# 4028_bcd.net
KiCad netlist of a schematic drawn in EAGLE
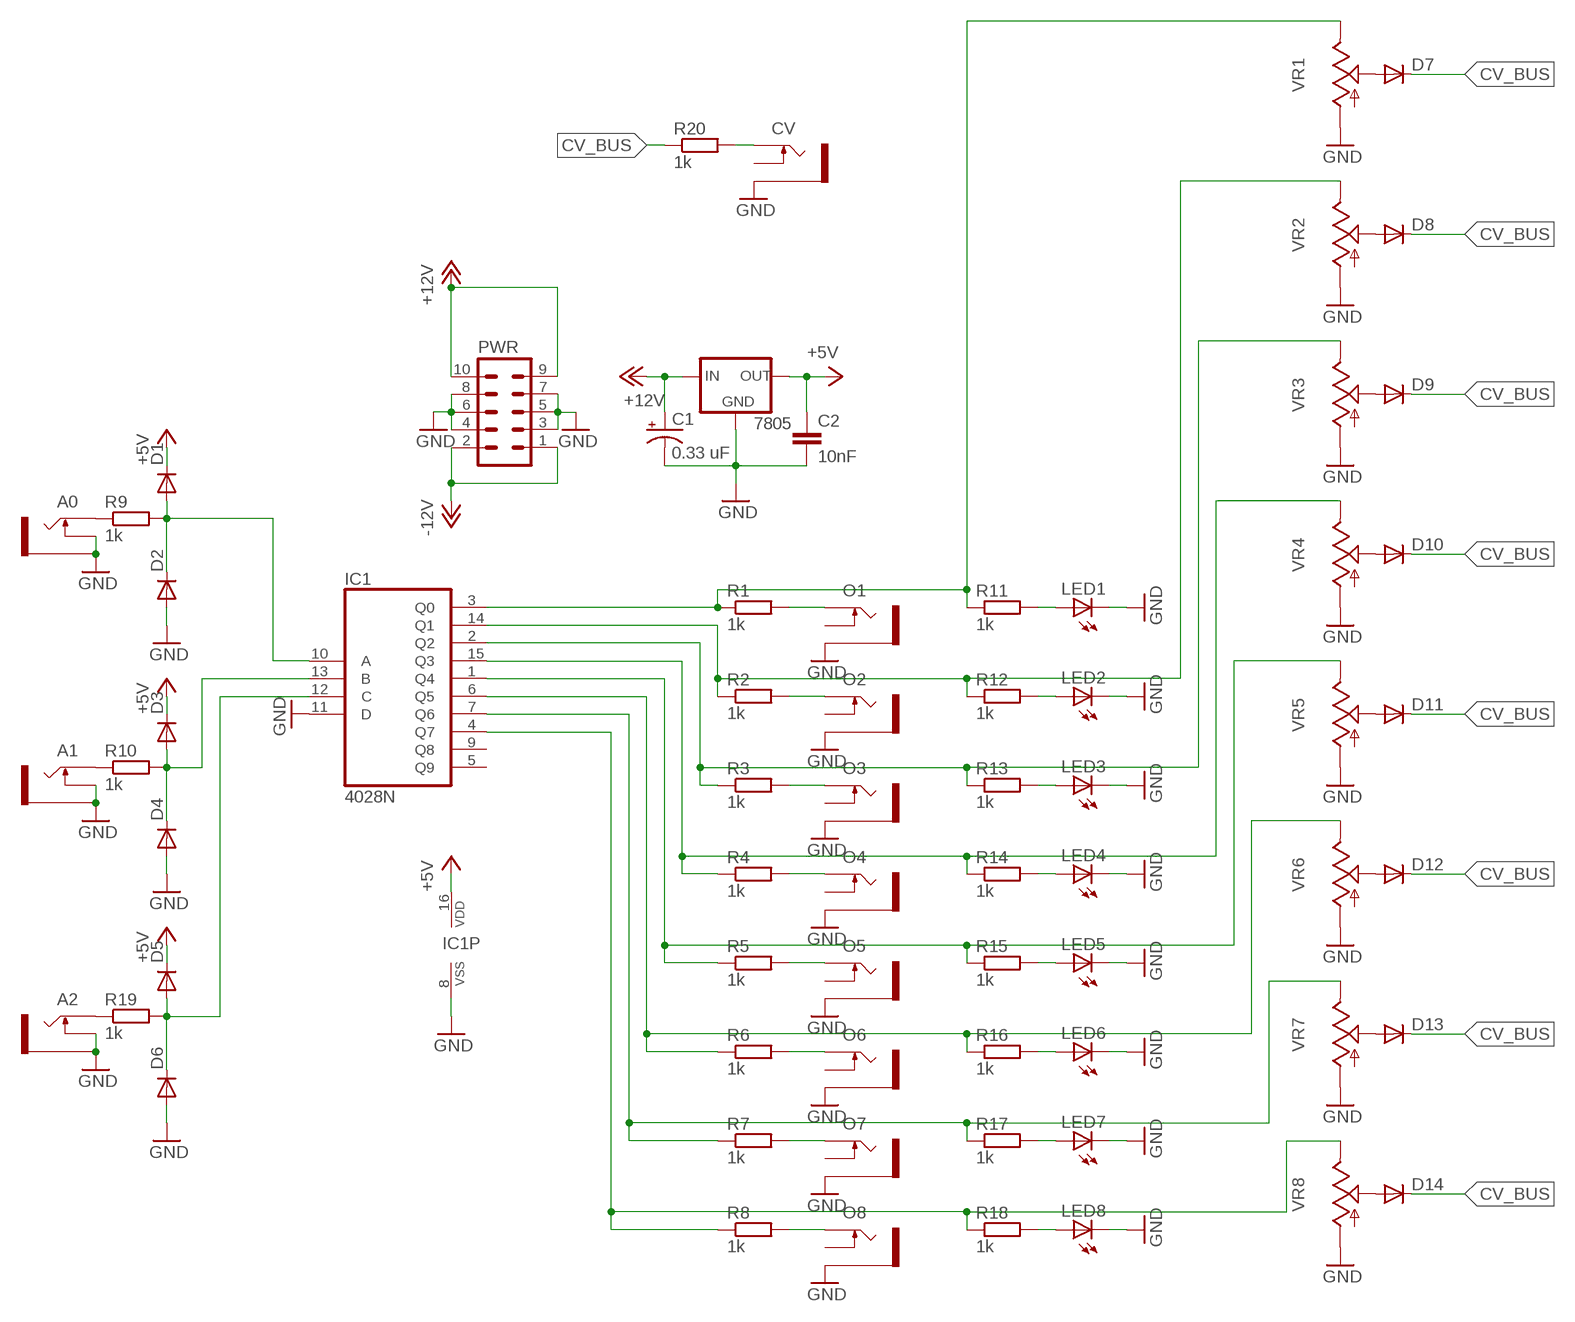
[diagram p0: schematic, sheet 1]

(export (version "E")
  (design (tool "Eeschema 10.0.6"))
  (components
    (comp (ref "7805")
      (value "78XXS")
      (footprint "eagle-import:78XXS")
      (libsource (lib "eagle-import") (part "78XXS"))
    )
    (comp (ref "A0")
      (value "THONKICONNNEW")
      (footprint "eagle-import:WQP-PJ301M-12_JACK")
      (libsource (lib "eagle-import") (part "THONKICONNNEW"))
    )
    (comp (ref "A1")
      (value "THONKICONNNEW")
      (footprint "eagle-import:WQP-PJ301M-12_JACK")
      (libsource (lib "eagle-import") (part "THONKICONNNEW"))
    )
    (comp (ref "A2")
      (value "THONKICONNNEW")
      (footprint "eagle-import:WQP-PJ301M-12_JACK")
      (libsource (lib "eagle-import") (part "THONKICONNNEW"))
    )
    (comp (ref "C1")
      (value "0.33 uF")
      (footprint "eagle-import:E2,5-7")
      (libsource (lib "eagle-import") (part "CPOL-USE2.5-7"))
    )
    (comp (ref "C2")
      (value "10nF")
      (footprint "eagle-import:CAP-PTH-10MM")
      (libsource (lib "eagle-import") (part "10NF-PTH-10MM-10000V-1-%"))
    )
    (comp (ref "CV")
      (value "THONKICONNNEW")
      (footprint "eagle-import:WQP-PJ301M-12_JACK")
      (libsource (lib "eagle-import") (part "THONKICONNNEW"))
    )
    (comp (ref "D1")
      (value "SMALL_DIODEDO35-7")
      (footprint "eagle-import:DO35-7")
      (libsource (lib "eagle-import") (part "SMALL_DIODEDO35-7"))
    )
    (comp (ref "D2")
      (value "SMALL_DIODEDO35-7")
      (footprint "eagle-import:DO35-7")
      (libsource (lib "eagle-import") (part "SMALL_DIODEDO35-7"))
    )
    (comp (ref "D3")
      (value "SMALL_DIODEDO35-7")
      (footprint "eagle-import:DO35-7")
      (libsource (lib "eagle-import") (part "SMALL_DIODEDO35-7"))
    )
    (comp (ref "D4")
      (value "SMALL_DIODEDO35-7")
      (footprint "eagle-import:DO35-7")
      (libsource (lib "eagle-import") (part "SMALL_DIODEDO35-7"))
    )
    (comp (ref "D5")
      (value "SMALL_DIODEDO35-7")
      (footprint "eagle-import:DO35-7")
      (libsource (lib "eagle-import") (part "SMALL_DIODEDO35-7"))
    )
    (comp (ref "D6")
      (value "SMALL_DIODEDO35-7")
      (footprint "eagle-import:DO35-7")
      (libsource (lib "eagle-import") (part "SMALL_DIODEDO35-7"))
    )
    (comp (ref "D7")
      (value "SMALL_DIODEDO35-7")
      (footprint "eagle-import:DO35-7")
      (libsource (lib "eagle-import") (part "SMALL_DIODEDO35-7"))
    )
    (comp (ref "D8")
      (value "SMALL_DIODEDO35-7")
      (footprint "eagle-import:DO35-7")
      (libsource (lib "eagle-import") (part "SMALL_DIODEDO35-7"))
    )
    (comp (ref "D9")
      (value "SMALL_DIODEDO35-7")
      (footprint "eagle-import:DO35-7")
      (libsource (lib "eagle-import") (part "SMALL_DIODEDO35-7"))
    )
    (comp (ref "D10")
      (value "SMALL_DIODEDO35-7")
      (footprint "eagle-import:DO35-7")
      (libsource (lib "eagle-import") (part "SMALL_DIODEDO35-7"))
    )
    (comp (ref "D11")
      (value "SMALL_DIODEDO35-7")
      (footprint "eagle-import:DO35-7")
      (libsource (lib "eagle-import") (part "SMALL_DIODEDO35-7"))
    )
    (comp (ref "D12")
      (value "SMALL_DIODEDO35-7")
      (footprint "eagle-import:DO35-7")
      (libsource (lib "eagle-import") (part "SMALL_DIODEDO35-7"))
    )
    (comp (ref "D13")
      (value "SMALL_DIODEDO35-7")
      (footprint "eagle-import:DO35-7")
      (libsource (lib "eagle-import") (part "SMALL_DIODEDO35-7"))
    )
    (comp (ref "D14")
      (value "SMALL_DIODEDO35-7")
      (footprint "eagle-import:DO35-7")
      (libsource (lib "eagle-import") (part "SMALL_DIODEDO35-7"))
    )
    (comp (ref "IC1")
      (value "4028N")
      (footprint "eagle-import:DIL16")
      (libsource (lib "eagle-import") (part "4028N"))
    )
    (comp (ref "LED1")
      (value "LED3MM")
      (footprint "eagle-import:LED3MM")
      (libsource (lib "eagle-import") (part "LED3MM"))
    )
    (comp (ref "LED2")
      (value "LED3MM")
      (footprint "eagle-import:LED3MM")
      (libsource (lib "eagle-import") (part "LED3MM"))
    )
    (comp (ref "LED3")
      (value "LED3MM")
      (footprint "eagle-import:LED3MM")
      (libsource (lib "eagle-import") (part "LED3MM"))
    )
    (comp (ref "LED4")
      (value "LED3MM")
      (footprint "eagle-import:LED3MM")
      (libsource (lib "eagle-import") (part "LED3MM"))
    )
    (comp (ref "LED5")
      (value "LED3MM")
      (footprint "eagle-import:LED3MM")
      (libsource (lib "eagle-import") (part "LED3MM"))
    )
    (comp (ref "LED6")
      (value "LED3MM")
      (footprint "eagle-import:LED3MM")
      (libsource (lib "eagle-import") (part "LED3MM"))
    )
    (comp (ref "LED7")
      (value "LED3MM")
      (footprint "eagle-import:LED3MM")
      (libsource (lib "eagle-import") (part "LED3MM"))
    )
    (comp (ref "LED8")
      (value "LED3MM")
      (footprint "eagle-import:LED3MM")
      (libsource (lib "eagle-import") (part "LED3MM"))
    )
    (comp (ref "O1")
      (value "THONKICONNNEW")
      (footprint "eagle-import:WQP-PJ301M-12_JACK")
      (libsource (lib "eagle-import") (part "THONKICONNNEW"))
    )
    (comp (ref "O2")
      (value "THONKICONNNEW")
      (footprint "eagle-import:WQP-PJ301M-12_JACK")
      (libsource (lib "eagle-import") (part "THONKICONNNEW"))
    )
    (comp (ref "O3")
      (value "THONKICONNNEW")
      (footprint "eagle-import:WQP-PJ301M-12_JACK")
      (libsource (lib "eagle-import") (part "THONKICONNNEW"))
    )
    (comp (ref "O4")
      (value "THONKICONNNEW")
      (footprint "eagle-import:WQP-PJ301M-12_JACK")
      (libsource (lib "eagle-import") (part "THONKICONNNEW"))
    )
    (comp (ref "O5")
      (value "THONKICONNNEW")
      (footprint "eagle-import:WQP-PJ301M-12_JACK")
      (libsource (lib "eagle-import") (part "THONKICONNNEW"))
    )
    (comp (ref "O6")
      (value "THONKICONNNEW")
      (footprint "eagle-import:WQP-PJ301M-12_JACK")
      (libsource (lib "eagle-import") (part "THONKICONNNEW"))
    )
    (comp (ref "O7")
      (value "THONKICONNNEW")
      (footprint "eagle-import:WQP-PJ301M-12_JACK")
      (libsource (lib "eagle-import") (part "THONKICONNNEW"))
    )
    (comp (ref "O8")
      (value "THONKICONNNEW")
      (footprint "eagle-import:WQP-PJ301M-12_JACK")
      (libsource (lib "eagle-import") (part "THONKICONNNEW"))
    )
    (comp (ref "PWR")
      (value "EURO_POWER_HEADERFAT_PADS")
      (footprint "eagle-import:EURO_PWR_HEADER_FAT")
      (libsource (lib "eagle-import") (part "EURO_POWER_HEADERFAT_PADS"))
    )
    (comp (ref "R1")
      (value "1k")
      (footprint "eagle-import:7MM_RESISTOR")
      (libsource (lib "eagle-import") (part "RESISTOR7MM"))
    )
    (comp (ref "R2")
      (value "1k")
      (footprint "eagle-import:7MM_RESISTOR")
      (libsource (lib "eagle-import") (part "RESISTOR7MM"))
    )
    (comp (ref "R3")
      (value "1k")
      (footprint "eagle-import:7MM_RESISTOR")
      (libsource (lib "eagle-import") (part "RESISTOR7MM"))
    )
    (comp (ref "R4")
      (value "1k")
      (footprint "eagle-import:7MM_RESISTOR")
      (libsource (lib "eagle-import") (part "RESISTOR7MM"))
    )
    (comp (ref "R5")
      (value "1k")
      (footprint "eagle-import:7MM_RESISTOR")
      (libsource (lib "eagle-import") (part "RESISTOR7MM"))
    )
    (comp (ref "R6")
      (value "1k")
      (footprint "eagle-import:7MM_RESISTOR")
      (libsource (lib "eagle-import") (part "RESISTOR7MM"))
    )
    (comp (ref "R7")
      (value "1k")
      (footprint "eagle-import:7MM_RESISTOR")
      (libsource (lib "eagle-import") (part "RESISTOR7MM"))
    )
    (comp (ref "R8")
      (value "1k")
      (footprint "eagle-import:7MM_RESISTOR")
      (libsource (lib "eagle-import") (part "RESISTOR7MM"))
    )
    (comp (ref "R9")
      (value "1k")
      (footprint "eagle-import:7MM_RESISTOR")
      (libsource (lib "eagle-import") (part "RESISTOR7MM"))
    )
    (comp (ref "R10")
      (value "1k")
      (footprint "eagle-import:7MM_RESISTOR")
      (libsource (lib "eagle-import") (part "RESISTOR7MM"))
    )
    (comp (ref "R11")
      (value "1k")
      (footprint "eagle-import:7MM_RESISTOR")
      (libsource (lib "eagle-import") (part "RESISTOR7MM"))
    )
    (comp (ref "R12")
      (value "1k")
      (footprint "eagle-import:7MM_RESISTOR")
      (libsource (lib "eagle-import") (part "RESISTOR7MM"))
    )
    (comp (ref "R13")
      (value "1k")
      (footprint "eagle-import:7MM_RESISTOR")
      (libsource (lib "eagle-import") (part "RESISTOR7MM"))
    )
    (comp (ref "R14")
      (value "1k")
      (footprint "eagle-import:7MM_RESISTOR")
      (libsource (lib "eagle-import") (part "RESISTOR7MM"))
    )
    (comp (ref "R15")
      (value "1k")
      (footprint "eagle-import:7MM_RESISTOR")
      (libsource (lib "eagle-import") (part "RESISTOR7MM"))
    )
    (comp (ref "R16")
      (value "1k")
      (footprint "eagle-import:7MM_RESISTOR")
      (libsource (lib "eagle-import") (part "RESISTOR7MM"))
    )
    (comp (ref "R17")
      (value "1k")
      (footprint "eagle-import:7MM_RESISTOR")
      (libsource (lib "eagle-import") (part "RESISTOR7MM"))
    )
    (comp (ref "R18")
      (value "1k")
      (footprint "eagle-import:7MM_RESISTOR")
      (libsource (lib "eagle-import") (part "RESISTOR7MM"))
    )
    (comp (ref "R19")
      (value "1k")
      (footprint "eagle-import:7MM_RESISTOR")
      (libsource (lib "eagle-import") (part "RESISTOR7MM"))
    )
    (comp (ref "R20")
      (value "1k")
      (footprint "eagle-import:7MM_RESISTOR")
      (libsource (lib "eagle-import") (part "RESISTOR7MM"))
    )
    (comp (ref "VR1")
      (value "9MM_SNAP-IN_POT_")
      (footprint "eagle-import:9MM_SNAP-IN_POT")
      (libsource (lib "eagle-import") (part "9MM_SNAP-IN_POT_"))
    )
    (comp (ref "VR2")
      (value "9MM_SNAP-IN_POT_")
      (footprint "eagle-import:9MM_SNAP-IN_POT")
      (libsource (lib "eagle-import") (part "9MM_SNAP-IN_POT_"))
    )
    (comp (ref "VR3")
      (value "9MM_SNAP-IN_POT_")
      (footprint "eagle-import:9MM_SNAP-IN_POT")
      (libsource (lib "eagle-import") (part "9MM_SNAP-IN_POT_"))
    )
    (comp (ref "VR4")
      (value "9MM_SNAP-IN_POT_")
      (footprint "eagle-import:9MM_SNAP-IN_POT")
      (libsource (lib "eagle-import") (part "9MM_SNAP-IN_POT_"))
    )
    (comp (ref "VR5")
      (value "9MM_SNAP-IN_POT_")
      (footprint "eagle-import:9MM_SNAP-IN_POT")
      (libsource (lib "eagle-import") (part "9MM_SNAP-IN_POT_"))
    )
    (comp (ref "VR6")
      (value "9MM_SNAP-IN_POT_")
      (footprint "eagle-import:9MM_SNAP-IN_POT")
      (libsource (lib "eagle-import") (part "9MM_SNAP-IN_POT_"))
    )
    (comp (ref "VR7")
      (value "9MM_SNAP-IN_POT_")
      (footprint "eagle-import:9MM_SNAP-IN_POT")
      (libsource (lib "eagle-import") (part "9MM_SNAP-IN_POT_"))
    )
    (comp (ref "VR8")
      (value "9MM_SNAP-IN_POT_")
      (footprint "eagle-import:9MM_SNAP-IN_POT")
      (libsource (lib "eagle-import") (part "9MM_SNAP-IN_POT_"))
    )
  )
  (nets
    (net (code "1") (name "+5V") (class "Default")
      (node (ref "7805") (pin "OUT") (pinfunction "OUT_OUT") (pintype "passive"))
      (node (ref "C2") (pin "1") (pinfunction "1_1") (pintype "passive"))
      (node (ref "D1") (pin "C") (pinfunction "C_C") (pintype "passive"))
      (node (ref "D3") (pin "C") (pinfunction "C_C") (pintype "passive"))
      (node (ref "D5") (pin "C") (pinfunction "C_C") (pintype "passive"))
      (node (ref "IC1") (pin "16") (pinfunction "VDD_16") (pintype "power_in"))
    )
    (net (code "2") (name "+12V") (class "Default")
      (node (ref "7805") (pin "IN") (pinfunction "IN_IN") (pintype "input"))
      (node (ref "C1") (pin "+") (pinfunction "+_+") (pintype "passive"))
      (node (ref "PWR") (pin "10") (pinfunction "10_10") (pintype "passive"))
      (node (ref "PWR") (pin "9") (pinfunction "9_9") (pintype "passive"))
    )
    (net (code "3") (name "-12V") (class "Default")
      (node (ref "PWR") (pin "1") (pinfunction "1_1") (pintype "passive"))
      (node (ref "PWR") (pin "2") (pinfunction "2_2") (pintype "passive"))
    )
    (net (code "4") (name "CV_BUS") (class "Default")
      (node (ref "D10") (pin "C") (pinfunction "C_C") (pintype "passive"))
      (node (ref "D11") (pin "C") (pinfunction "C_C") (pintype "passive"))
      (node (ref "D12") (pin "C") (pinfunction "C_C") (pintype "passive"))
      (node (ref "D13") (pin "C") (pinfunction "C_C") (pintype "passive"))
      (node (ref "D14") (pin "C") (pinfunction "C_C") (pintype "passive"))
      (node (ref "D7") (pin "C") (pinfunction "C_C") (pintype "passive"))
      (node (ref "D8") (pin "C") (pinfunction "C_C") (pintype "passive"))
      (node (ref "D9") (pin "C") (pinfunction "C_C") (pintype "passive"))
      (node (ref "R20") (pin "1") (pinfunction "1_1") (pintype "passive"))
    )
    (net (code "5") (name "GND") (class "Default")
      (node (ref "7805") (pin "GND") (pinfunction "GND_GND") (pintype "input"))
      (node (ref "A0") (pin "P$2_SWITCH") (pinfunction "SWITCH_P$2_SWITCH") (pintype "passive"))
      (node (ref "A0") (pin "P$3_SLEEVE") (pinfunction "SLEEVE_P$3_SLEEVE") (pintype "passive"))
      (node (ref "A1") (pin "P$2_SWITCH") (pinfunction "SWITCH_P$2_SWITCH") (pintype "passive"))
      (node (ref "A1") (pin "P$3_SLEEVE") (pinfunction "SLEEVE_P$3_SLEEVE") (pintype "passive"))
      (node (ref "A2") (pin "P$2_SWITCH") (pinfunction "SWITCH_P$2_SWITCH") (pintype "passive"))
      (node (ref "A2") (pin "P$3_SLEEVE") (pinfunction "SLEEVE_P$3_SLEEVE") (pintype "passive"))
      (node (ref "C1") (pin "-") (pinfunction "-_-") (pintype "passive"))
      (node (ref "C2") (pin "2") (pinfunction "2_2") (pintype "passive"))
      (node (ref "CV") (pin "P$3_SLEEVE") (pinfunction "SLEEVE_P$3_SLEEVE") (pintype "passive"))
      (node (ref "D2") (pin "A") (pinfunction "A_A") (pintype "passive"))
      (node (ref "D4") (pin "A") (pinfunction "A_A") (pintype "passive"))
      (node (ref "D6") (pin "A") (pinfunction "A_A") (pintype "passive"))
      (node (ref "IC1") (pin "11") (pinfunction "D_11") (pintype "input"))
      (node (ref "IC1") (pin "8") (pinfunction "VSS_8") (pintype "power_in"))
      (node (ref "LED1") (pin "K") (pinfunction "C_K") (pintype "passive"))
      (node (ref "LED2") (pin "K") (pinfunction "C_K") (pintype "passive"))
      (node (ref "LED3") (pin "K") (pinfunction "C_K") (pintype "passive"))
      (node (ref "LED4") (pin "K") (pinfunction "C_K") (pintype "passive"))
      (node (ref "LED5") (pin "K") (pinfunction "C_K") (pintype "passive"))
      (node (ref "LED6") (pin "K") (pinfunction "C_K") (pintype "passive"))
      (node (ref "LED7") (pin "K") (pinfunction "C_K") (pintype "passive"))
      (node (ref "LED8") (pin "K") (pinfunction "C_K") (pintype "passive"))
      (node (ref "O1") (pin "P$3_SLEEVE") (pinfunction "SLEEVE_P$3_SLEEVE") (pintype "passive"))
      (node (ref "O2") (pin "P$3_SLEEVE") (pinfunction "SLEEVE_P$3_SLEEVE") (pintype "passive"))
      (node (ref "O3") (pin "P$3_SLEEVE") (pinfunction "SLEEVE_P$3_SLEEVE") (pintype "passive"))
      (node (ref "O4") (pin "P$3_SLEEVE") (pinfunction "SLEEVE_P$3_SLEEVE") (pintype "passive"))
      (node (ref "O5") (pin "P$3_SLEEVE") (pinfunction "SLEEVE_P$3_SLEEVE") (pintype "passive"))
      (node (ref "O6") (pin "P$3_SLEEVE") (pinfunction "SLEEVE_P$3_SLEEVE") (pintype "passive"))
      (node (ref "O7") (pin "P$3_SLEEVE") (pinfunction "SLEEVE_P$3_SLEEVE") (pintype "passive"))
      (node (ref "O8") (pin "P$3_SLEEVE") (pinfunction "SLEEVE_P$3_SLEEVE") (pintype "passive"))
      (node (ref "PWR") (pin "3") (pinfunction "3_3") (pintype "passive"))
      (node (ref "PWR") (pin "4") (pinfunction "4_4") (pintype "passive"))
      (node (ref "PWR") (pin "5") (pinfunction "5_5") (pintype "passive"))
      (node (ref "PWR") (pin "6") (pinfunction "6_6") (pintype "passive"))
      (node (ref "PWR") (pin "7") (pinfunction "7_7") (pintype "passive"))
      (node (ref "PWR") (pin "8") (pinfunction "8_8") (pintype "passive"))
      (node (ref "VR1") (pin "1") (pinfunction "A_1") (pintype "passive"))
      (node (ref "VR2") (pin "1") (pinfunction "A_1") (pintype "passive"))
      (node (ref "VR3") (pin "1") (pinfunction "A_1") (pintype "passive"))
      (node (ref "VR4") (pin "1") (pinfunction "A_1") (pintype "passive"))
      (node (ref "VR5") (pin "1") (pinfunction "A_1") (pintype "passive"))
      (node (ref "VR6") (pin "1") (pinfunction "A_1") (pintype "passive"))
      (node (ref "VR7") (pin "1") (pinfunction "A_1") (pintype "passive"))
      (node (ref "VR8") (pin "1") (pinfunction "A_1") (pintype "passive"))
    )
    (net (code "6") (name "Net-(A0-TIP)") (class "Default")
      (node (ref "A0") (pin "P$1_TIP") (pinfunction "TIP_P$1_TIP") (pintype "passive"))
      (node (ref "R9") (pin "1") (pinfunction "1_1") (pintype "passive"))
    )
    (net (code "7") (name "Net-(A1-TIP)") (class "Default")
      (node (ref "A1") (pin "P$1_TIP") (pinfunction "TIP_P$1_TIP") (pintype "passive"))
      (node (ref "R10") (pin "1") (pinfunction "1_1") (pintype "passive"))
    )
    (net (code "8") (name "Net-(A2-TIP)") (class "Default")
      (node (ref "A2") (pin "P$1_TIP") (pinfunction "TIP_P$1_TIP") (pintype "passive"))
      (node (ref "R19") (pin "1") (pinfunction "1_1") (pintype "passive"))
    )
    (net (code "9") (name "Net-(CV-TIP)") (class "Default")
      (node (ref "CV") (pin "P$1_TIP") (pinfunction "TIP_P$1_TIP") (pintype "passive"))
      (node (ref "R20") (pin "2") (pinfunction "2_2") (pintype "passive"))
    )
    (net (code "10") (name "Net-(IC1A-A)") (class "Default")
      (node (ref "D1") (pin "A") (pinfunction "A_A") (pintype "passive"))
      (node (ref "D2") (pin "C") (pinfunction "C_C") (pintype "passive"))
      (node (ref "IC1") (pin "10") (pinfunction "A_10") (pintype "input"))
      (node (ref "R9") (pin "2") (pinfunction "2_2") (pintype "passive"))
    )
    (net (code "11") (name "Net-(IC1A-B)") (class "Default")
      (node (ref "D3") (pin "A") (pinfunction "A_A") (pintype "passive"))
      (node (ref "D4") (pin "C") (pinfunction "C_C") (pintype "passive"))
      (node (ref "IC1") (pin "13") (pinfunction "B_13") (pintype "input"))
      (node (ref "R10") (pin "2") (pinfunction "2_2") (pintype "passive"))
    )
    (net (code "12") (name "Net-(IC1A-C)") (class "Default")
      (node (ref "D5") (pin "A") (pinfunction "A_A") (pintype "passive"))
      (node (ref "D6") (pin "C") (pinfunction "C_C") (pintype "passive"))
      (node (ref "IC1") (pin "12") (pinfunction "C_12") (pintype "input"))
      (node (ref "R19") (pin "2") (pinfunction "2_2") (pintype "passive"))
    )
    (net (code "13") (name "Net-(IC1A-Q0)") (class "Default")
      (node (ref "IC1") (pin "3") (pinfunction "Q0_3") (pintype "output"))
      (node (ref "R1") (pin "1") (pinfunction "1_1") (pintype "passive"))
      (node (ref "R11") (pin "1") (pinfunction "1_1") (pintype "passive"))
      (node (ref "VR1") (pin "3") (pinfunction "E_3") (pintype "passive"))
    )
    (net (code "14") (name "Net-(IC1A-Q1)") (class "Default")
      (node (ref "IC1") (pin "14") (pinfunction "Q1_14") (pintype "output"))
      (node (ref "R12") (pin "1") (pinfunction "1_1") (pintype "passive"))
      (node (ref "R2") (pin "1") (pinfunction "1_1") (pintype "passive"))
      (node (ref "VR2") (pin "3") (pinfunction "E_3") (pintype "passive"))
    )
    (net (code "15") (name "Net-(IC1A-Q2)") (class "Default")
      (node (ref "IC1") (pin "2") (pinfunction "Q2_2") (pintype "output"))
      (node (ref "R13") (pin "1") (pinfunction "1_1") (pintype "passive"))
      (node (ref "R3") (pin "1") (pinfunction "1_1") (pintype "passive"))
      (node (ref "VR3") (pin "3") (pinfunction "E_3") (pintype "passive"))
    )
    (net (code "16") (name "Net-(IC1A-Q3)") (class "Default")
      (node (ref "IC1") (pin "15") (pinfunction "Q3_15") (pintype "output"))
      (node (ref "R14") (pin "1") (pinfunction "1_1") (pintype "passive"))
      (node (ref "R4") (pin "1") (pinfunction "1_1") (pintype "passive"))
      (node (ref "VR4") (pin "3") (pinfunction "E_3") (pintype "passive"))
    )
    (net (code "17") (name "Net-(IC1A-Q4)") (class "Default")
      (node (ref "IC1") (pin "1") (pinfunction "Q4_1") (pintype "output"))
      (node (ref "R15") (pin "1") (pinfunction "1_1") (pintype "passive"))
      (node (ref "R5") (pin "1") (pinfunction "1_1") (pintype "passive"))
      (node (ref "VR5") (pin "3") (pinfunction "E_3") (pintype "passive"))
    )
    (net (code "18") (name "Net-(IC1A-Q5)") (class "Default")
      (node (ref "IC1") (pin "6") (pinfunction "Q5_6") (pintype "output"))
      (node (ref "R16") (pin "1") (pinfunction "1_1") (pintype "passive"))
      (node (ref "R6") (pin "1") (pinfunction "1_1") (pintype "passive"))
      (node (ref "VR6") (pin "3") (pinfunction "E_3") (pintype "passive"))
    )
    (net (code "19") (name "Net-(IC1A-Q6)") (class "Default")
      (node (ref "IC1") (pin "7") (pinfunction "Q6_7") (pintype "output"))
      (node (ref "R17") (pin "1") (pinfunction "1_1") (pintype "passive"))
      (node (ref "R7") (pin "1") (pinfunction "1_1") (pintype "passive"))
      (node (ref "VR7") (pin "3") (pinfunction "E_3") (pintype "passive"))
    )
    (net (code "20") (name "Net-(IC1A-Q7)") (class "Default")
      (node (ref "IC1") (pin "4") (pinfunction "Q7_4") (pintype "output"))
      (node (ref "R18") (pin "1") (pinfunction "1_1") (pintype "passive"))
      (node (ref "R8") (pin "1") (pinfunction "1_1") (pintype "passive"))
      (node (ref "VR8") (pin "3") (pinfunction "E_3") (pintype "passive"))
    )
    (net (code "21") (name "Net-(LED1-PadA)") (class "Default")
      (node (ref "LED1") (pin "A") (pinfunction "A_A") (pintype "passive"))
      (node (ref "R11") (pin "2") (pinfunction "2_2") (pintype "passive"))
    )
    (net (code "22") (name "Net-(LED2-PadA)") (class "Default")
      (node (ref "LED2") (pin "A") (pinfunction "A_A") (pintype "passive"))
      (node (ref "R12") (pin "2") (pinfunction "2_2") (pintype "passive"))
    )
    (net (code "23") (name "Net-(LED3-PadA)") (class "Default")
      (node (ref "LED3") (pin "A") (pinfunction "A_A") (pintype "passive"))
      (node (ref "R13") (pin "2") (pinfunction "2_2") (pintype "passive"))
    )
    (net (code "24") (name "Net-(LED4-PadA)") (class "Default")
      (node (ref "LED4") (pin "A") (pinfunction "A_A") (pintype "passive"))
      (node (ref "R14") (pin "2") (pinfunction "2_2") (pintype "passive"))
    )
    (net (code "25") (name "Net-(LED5-PadA)") (class "Default")
      (node (ref "LED5") (pin "A") (pinfunction "A_A") (pintype "passive"))
      (node (ref "R15") (pin "2") (pinfunction "2_2") (pintype "passive"))
    )
    (net (code "26") (name "Net-(LED6-PadA)") (class "Default")
      (node (ref "LED6") (pin "A") (pinfunction "A_A") (pintype "passive"))
      (node (ref "R16") (pin "2") (pinfunction "2_2") (pintype "passive"))
    )
    (net (code "27") (name "Net-(LED7-PadA)") (class "Default")
      (node (ref "LED7") (pin "A") (pinfunction "A_A") (pintype "passive"))
      (node (ref "R17") (pin "2") (pinfunction "2_2") (pintype "passive"))
    )
    (net (code "28") (name "Net-(LED8-PadA)") (class "Default")
      (node (ref "LED8") (pin "A") (pinfunction "A_A") (pintype "passive"))
      (node (ref "R18") (pin "2") (pinfunction "2_2") (pintype "passive"))
    )
    (net (code "29") (name "Net-(O1-TIP)") (class "Default")
      (node (ref "O1") (pin "P$1_TIP") (pinfunction "TIP_P$1_TIP") (pintype "passive"))
      (node (ref "R1") (pin "2") (pinfunction "2_2") (pintype "passive"))
    )
    (net (code "30") (name "Net-(O2-TIP)") (class "Default")
      (node (ref "O2") (pin "P$1_TIP") (pinfunction "TIP_P$1_TIP") (pintype "passive"))
      (node (ref "R2") (pin "2") (pinfunction "2_2") (pintype "passive"))
    )
    (net (code "31") (name "Net-(O3-TIP)") (class "Default")
      (node (ref "O3") (pin "P$1_TIP") (pinfunction "TIP_P$1_TIP") (pintype "passive"))
      (node (ref "R3") (pin "2") (pinfunction "2_2") (pintype "passive"))
    )
    (net (code "32") (name "Net-(O4-TIP)") (class "Default")
      (node (ref "O4") (pin "P$1_TIP") (pinfunction "TIP_P$1_TIP") (pintype "passive"))
      (node (ref "R4") (pin "2") (pinfunction "2_2") (pintype "passive"))
    )
    (net (code "33") (name "Net-(O5-TIP)") (class "Default")
      (node (ref "O5") (pin "P$1_TIP") (pinfunction "TIP_P$1_TIP") (pintype "passive"))
      (node (ref "R5") (pin "2") (pinfunction "2_2") (pintype "passive"))
    )
    (net (code "34") (name "Net-(O6-TIP)") (class "Default")
      (node (ref "O6") (pin "P$1_TIP") (pinfunction "TIP_P$1_TIP") (pintype "passive"))
      (node (ref "R6") (pin "2") (pinfunction "2_2") (pintype "passive"))
    )
    (net (code "35") (name "Net-(O7-TIP)") (class "Default")
      (node (ref "O7") (pin "P$1_TIP") (pinfunction "TIP_P$1_TIP") (pintype "passive"))
      (node (ref "R7") (pin "2") (pinfunction "2_2") (pintype "passive"))
    )
    (net (code "36") (name "Net-(O8-TIP)") (class "Default")
      (node (ref "O8") (pin "P$1_TIP") (pinfunction "TIP_P$1_TIP") (pintype "passive"))
      (node (ref "R8") (pin "2") (pinfunction "2_2") (pintype "passive"))
    )
    (net (code "37") (name "Net-(VR1-S)") (class "Default")
      (node (ref "D7") (pin "A") (pinfunction "A_A") (pintype "passive"))
      (node (ref "VR1") (pin "2") (pinfunction "S_2") (pintype "passive"))
    )
    (net (code "38") (name "Net-(VR2-S)") (class "Default")
      (node (ref "D8") (pin "A") (pinfunction "A_A") (pintype "passive"))
      (node (ref "VR2") (pin "2") (pinfunction "S_2") (pintype "passive"))
    )
    (net (code "39") (name "Net-(VR3-S)") (class "Default")
      (node (ref "D9") (pin "A") (pinfunction "A_A") (pintype "passive"))
      (node (ref "VR3") (pin "2") (pinfunction "S_2") (pintype "passive"))
    )
    (net (code "40") (name "Net-(VR4-S)") (class "Default")
      (node (ref "D10") (pin "A") (pinfunction "A_A") (pintype "passive"))
      (node (ref "VR4") (pin "2") (pinfunction "S_2") (pintype "passive"))
    )
    (net (code "41") (name "Net-(VR5-S)") (class "Default")
      (node (ref "D11") (pin "A") (pinfunction "A_A") (pintype "passive"))
      (node (ref "VR5") (pin "2") (pinfunction "S_2") (pintype "passive"))
    )
    (net (code "42") (name "Net-(VR6-S)") (class "Default")
      (node (ref "D12") (pin "A") (pinfunction "A_A") (pintype "passive"))
      (node (ref "VR6") (pin "2") (pinfunction "S_2") (pintype "passive"))
    )
    (net (code "43") (name "Net-(VR7-S)") (class "Default")
      (node (ref "D13") (pin "A") (pinfunction "A_A") (pintype "passive"))
      (node (ref "VR7") (pin "2") (pinfunction "S_2") (pintype "passive"))
    )
    (net (code "44") (name "Net-(VR8-S)") (class "Default")
      (node (ref "D14") (pin "A") (pinfunction "A_A") (pintype "passive"))
      (node (ref "VR8") (pin "2") (pinfunction "S_2") (pintype "passive"))
    )
    (net (code "45") (name "unconnected-(CV-SWITCH-PadP$2_SWITCH)") (class "Default")
      (node (ref "CV") (pin "P$2_SWITCH") (pinfunction "SWITCH_P$2_SWITCH") (pintype "passive"))
    )
    (net (code "46") (name "unconnected-(IC1A-Q8-Pad9)") (class "Default")
      (node (ref "IC1") (pin "9") (pinfunction "Q8_9") (pintype "output"))
    )
    (net (code "47") (name "unconnected-(IC1A-Q9-Pad5)") (class "Default")
      (node (ref "IC1") (pin "5") (pinfunction "Q9_5") (pintype "output"))
    )
    (net (code "48") (name "unconnected-(O1-SWITCH-PadP$2_SWITCH)") (class "Default")
      (node (ref "O1") (pin "P$2_SWITCH") (pinfunction "SWITCH_P$2_SWITCH") (pintype "passive"))
    )
    (net (code "49") (name "unconnected-(O2-SWITCH-PadP$2_SWITCH)") (class "Default")
      (node (ref "O2") (pin "P$2_SWITCH") (pinfunction "SWITCH_P$2_SWITCH") (pintype "passive"))
    )
    (net (code "50") (name "unconnected-(O3-SWITCH-PadP$2_SWITCH)") (class "Default")
      (node (ref "O3") (pin "P$2_SWITCH") (pinfunction "SWITCH_P$2_SWITCH") (pintype "passive"))
    )
    (net (code "51") (name "unconnected-(O4-SWITCH-PadP$2_SWITCH)") (class "Default")
      (node (ref "O4") (pin "P$2_SWITCH") (pinfunction "SWITCH_P$2_SWITCH") (pintype "passive"))
    )
    (net (code "52") (name "unconnected-(O5-SWITCH-PadP$2_SWITCH)") (class "Default")
      (node (ref "O5") (pin "P$2_SWITCH") (pinfunction "SWITCH_P$2_SWITCH") (pintype "passive"))
    )
    (net (code "53") (name "unconnected-(O6-SWITCH-PadP$2_SWITCH)") (class "Default")
      (node (ref "O6") (pin "P$2_SWITCH") (pinfunction "SWITCH_P$2_SWITCH") (pintype "passive"))
    )
    (net (code "54") (name "unconnected-(O7-SWITCH-PadP$2_SWITCH)") (class "Default")
      (node (ref "O7") (pin "P$2_SWITCH") (pinfunction "SWITCH_P$2_SWITCH") (pintype "passive"))
    )
    (net (code "55") (name "unconnected-(O8-SWITCH-PadP$2_SWITCH)") (class "Default")
      (node (ref "O8") (pin "P$2_SWITCH") (pinfunction "SWITCH_P$2_SWITCH") (pintype "passive"))
    )
  )
)
